# 12v_power.net
KiCad netlist of a schematic drawn in Altium Designer
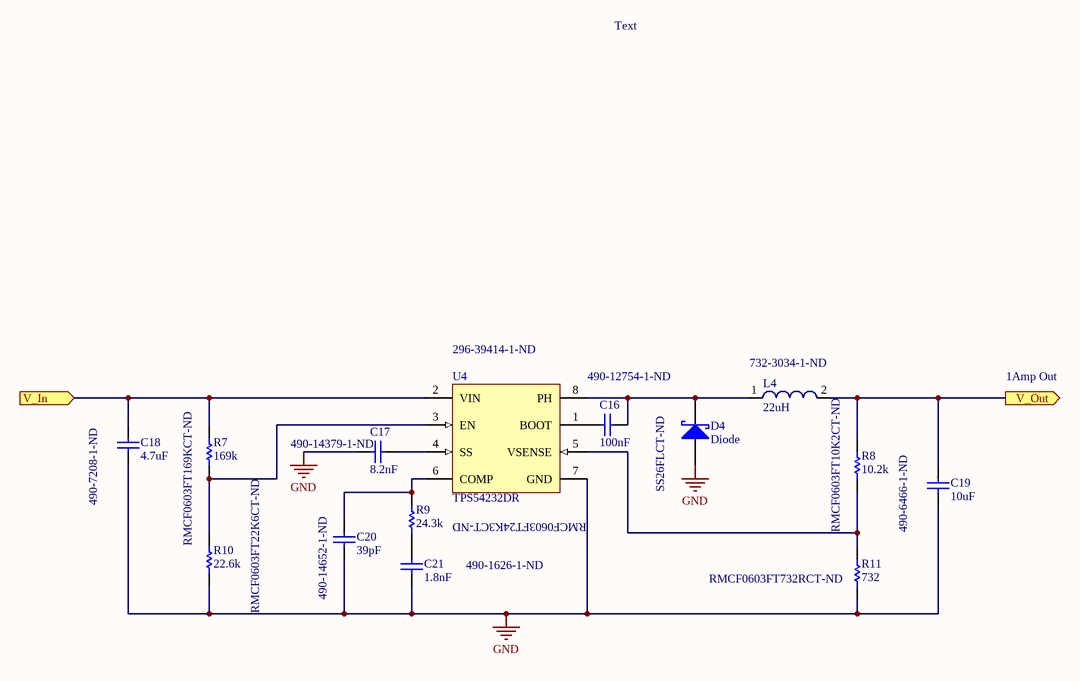
[diagram p0: 12v_power.SchDoc]

(export (version "E")
  (design (tool "Eeschema 10.0.6"))
  (components
    (comp (ref "C16")
      (value "Cap")
      (footprint "PCB-lllx3wppxbec679u3f24-1")
      (description "C Series 0805 22 uF 35 V ±10 % Tolerance X5R SMT Multilayer Ceramic Capacitor")
      (fields
        (field (name "MANUFACTURER PART NUMBER") "C2012X5R1V226M125AC")
        (field (name "CAPACITANCE") "100nF")
      )
      (libsource (lib "CommunityVault") (part "CMP-0d44c5e3fbabd283-1"))
    )
    (comp (ref "C17")
      (value "Cap")
      (footprint "PCB-lllx3wppxbec679u3f24-1")
      (description "C Series 0805 22 uF 35 V ±10 % Tolerance X5R SMT Multilayer Ceramic Capacitor")
      (fields
        (field (name "MANUFACTURER PART NUMBER") "C2012X5R1V226M125AC")
        (field (name "CAPACITANCE") "8.2nF")
      )
      (libsource (lib "CommunityVault") (part "CMP-0d44c5e3fbabd283-1"))
    )
    (comp (ref "C18")
      (value "Cap")
      (footprint "PCB-lllx3wppxbec679u3f24-1")
      (description "C Series 0805 22 uF 35 V ±10 % Tolerance X5R SMT Multilayer Ceramic Capacitor")
      (fields
        (field (name "MANUFACTURER PART NUMBER") "C2012X5R1V226M125AC")
        (field (name "CAPACITANCE") "4.7uF")
      )
      (libsource (lib "CommunityVault") (part "CMP-0d44c5e3fbabd283-1"))
    )
    (comp (ref "C19")
      (value "Cap")
      (footprint "PCB-lllx3wppxbec679u3f24-1")
      (description "C Series 0805 22 uF 35 V ±10 % Tolerance X5R SMT Multilayer Ceramic Capacitor")
      (fields
        (field (name "MANUFACTURER PART NUMBER") "C2012X5R1V226M125AC")
        (field (name "CAPACITANCE") "10uF")
      )
      (libsource (lib "CommunityVault") (part "CMP-0d44c5e3fbabd283-1"))
    )
    (comp (ref "C20")
      (value "Cap")
      (footprint "PCB-lllx3wppxbec679u3f24-1")
      (description "C Series 0805 22 uF 35 V ±10 % Tolerance X5R SMT Multilayer Ceramic Capacitor")
      (fields
        (field (name "MANUFACTURER PART NUMBER") "C2012X5R1V226M125AC")
        (field (name "CAPACITANCE") "39pF")
      )
      (libsource (lib "CommunityVault") (part "CMP-0d44c5e3fbabd283-1"))
    )
    (comp (ref "C21")
      (value "Cap")
      (footprint "PCB-lllx3wppxbec679u3f24-1")
      (description "C Series 0805 22 uF 35 V ±10 % Tolerance X5R SMT Multilayer Ceramic Capacitor")
      (fields
        (field (name "MANUFACTURER PART NUMBER") "C2012X5R1V226M125AC")
        (field (name "CAPACITANCE") "1.8nF")
      )
      (libsource (lib "CommunityVault") (part "CMP-0d44c5e3fbabd283-1"))
    )
    (comp (ref "D4")
      (value "Diode")
      (footprint "PCB-5gde02dk4bufsuch8kid-1")
      (description "Diode Schottky Barrier Rectifier 60V 2A 2-Pin SOD-123F T/R")
      (libsource (lib "CommunityVault") (part "SYM-0675ccf66d19d9b2-1"))
    )
    (comp (ref "L4")
      (value "22uH")
      (footprint "WE-SPC 4838")
      (description "SMD Shielded Power Inductor WE-SPC, L=22 µH")
      (libsource (lib "CommunityVault") (part "WE-IND-INDUCTOR-2"))
    )
    (comp (ref "R7")
      (value "169k")
      (footprint "R0603_A")
      (description "RC Series 0603 0.1 W 470 Ohms 5% ±100 ppm/°C SMT Thick Film Chip Resistor")
      (fields (field (name "MANUFACTURER PART NUMBER") "RC0603JR-07470RL"))
      (libsource (lib "CommunityVault") (part "CMP-d59d1ef5e9b70a5a-2"))
    )
    (comp (ref "R8")
      (value "10.2k")
      (footprint "R0603_A")
      (description "RC Series 0603 0.1 W 470 Ohms 5% ±100 ppm/°C SMT Thick Film Chip Resistor")
      (fields (field (name "MANUFACTURER PART NUMBER") "RC0603JR-07470RL"))
      (libsource (lib "CommunityVault") (part "CMP-d59d1ef5e9b70a5a-2"))
    )
    (comp (ref "R9")
      (value "24.3k")
      (footprint "R0603_A")
      (description "RC Series 0603 0.1 W 470 Ohms 5% ±100 ppm/°C SMT Thick Film Chip Resistor")
      (fields (field (name "MANUFACTURER PART NUMBER") "RC0603JR-07470RL"))
      (libsource (lib "CommunityVault") (part "CMP-d59d1ef5e9b70a5a-2"))
    )
    (comp (ref "R10")
      (value "22.6k")
      (footprint "R0603_A")
      (description "RC Series 0603 0.1 W 470 Ohms 5% ±100 ppm/°C SMT Thick Film Chip Resistor")
      (fields (field (name "MANUFACTURER PART NUMBER") "RC0603JR-07470RL"))
      (libsource (lib "CommunityVault") (part "CMP-d59d1ef5e9b70a5a-2"))
    )
    (comp (ref "R11")
      (value "732")
      (footprint "R0603_A")
      (description "RC Series 0603 0.1 W 470 Ohms 5% ±100 ppm/°C SMT Thick Film Chip Resistor")
      (fields (field (name "MANUFACTURER PART NUMBER") "RC0603JR-07470RL"))
      (libsource (lib "CommunityVault") (part "CMP-d59d1ef5e9b70a5a-2"))
    )
    (comp (ref "U4")
      (value "TPS54232DR")
      (footprint "D8_M")
      (libsource (lib "CommunityVault") (part "TI-TPS54232D8"))
    )
  )
  (nets
    (net (code "1") (name "/V_In") (class "Default")
      (node (ref "C18") (pin "1") (pinfunction "1_1") (pintype "passive"))
      (node (ref "R7") (pin "2") (pinfunction "2_2") (pintype "passive"))
      (node (ref "U4") (pin "2") (pinfunction "VIN_2") (pintype "power_in"))
    )
    (net (code "2") (name "/V_Out") (class "Default")
      (node (ref "C19") (pin "1") (pinfunction "1_1") (pintype "passive"))
      (node (ref "L4") (pin "2") (pinfunction "2_2") (pintype "passive"))
      (node (ref "R8") (pin "2") (pinfunction "2_2") (pintype "passive"))
    )
    (net (code "3") (name "GND") (class "Default")
      (node (ref "C17") (pin "1") (pinfunction "1_1") (pintype "passive"))
      (node (ref "C18") (pin "2") (pinfunction "2_2") (pintype "passive"))
      (node (ref "C19") (pin "2") (pinfunction "2_2") (pintype "passive"))
      (node (ref "C20") (pin "2") (pinfunction "2_2") (pintype "passive"))
      (node (ref "C21") (pin "2") (pinfunction "2_2") (pintype "passive"))
      (node (ref "D4") (pin "1") (pinfunction "A_1") (pintype "passive"))
      (node (ref "R10") (pin "1") (pinfunction "1_1") (pintype "passive"))
      (node (ref "R11") (pin "1") (pinfunction "1_1") (pintype "passive"))
      (node (ref "U4") (pin "7") (pinfunction "GND_7") (pintype "power_in"))
    )
    (net (code "4") (name "Net-(C21-Pad1)") (class "Default")
      (node (ref "C21") (pin "1") (pinfunction "1_1") (pintype "passive"))
      (node (ref "R9") (pin "1") (pinfunction "1_1") (pintype "passive"))
    )
    (net (code "5") (name "Net-(D4-K)") (class "Default")
      (node (ref "C16") (pin "1") (pinfunction "1_1") (pintype "passive"))
      (node (ref "D4") (pin "2") (pinfunction "K_2") (pintype "passive"))
      (node (ref "L4") (pin "1") (pinfunction "1_1") (pintype "passive"))
      (node (ref "U4") (pin "8") (pinfunction "PH_8") (pintype "power_in"))
    )
    (net (code "6") (name "Net-(U4-BOOT)") (class "Default")
      (node (ref "C16") (pin "2") (pinfunction "2_2") (pintype "passive"))
      (node (ref "U4") (pin "1") (pinfunction "BOOT_1") (pintype "passive"))
    )
    (net (code "7") (name "Net-(U4-COMP)") (class "Default")
      (node (ref "C20") (pin "1") (pinfunction "1_1") (pintype "passive"))
      (node (ref "R9") (pin "2") (pinfunction "2_2") (pintype "passive"))
      (node (ref "U4") (pin "6") (pinfunction "COMP_6") (pintype "passive"))
    )
    (net (code "8") (name "Net-(U4-EN)") (class "Default")
      (node (ref "R10") (pin "2") (pinfunction "2_2") (pintype "passive"))
      (node (ref "R7") (pin "1") (pinfunction "1_1") (pintype "passive"))
      (node (ref "U4") (pin "3") (pinfunction "EN_3") (pintype "input"))
    )
    (net (code "9") (name "Net-(U4-SS)") (class "Default")
      (node (ref "C17") (pin "2") (pinfunction "2_2") (pintype "passive"))
      (node (ref "U4") (pin "4") (pinfunction "SS_4") (pintype "input"))
    )
    (net (code "10") (name "Net-(U4-VSENSE)") (class "Default")
      (node (ref "R11") (pin "2") (pinfunction "2_2") (pintype "passive"))
      (node (ref "R8") (pin "1") (pinfunction "1_1") (pintype "passive"))
      (node (ref "U4") (pin "5") (pinfunction "VSENSE_5") (pintype "input"))
    )
  )
)
